# ZxUartAdapter.net
KiCad netlist of a schematic drawn in EAGLE
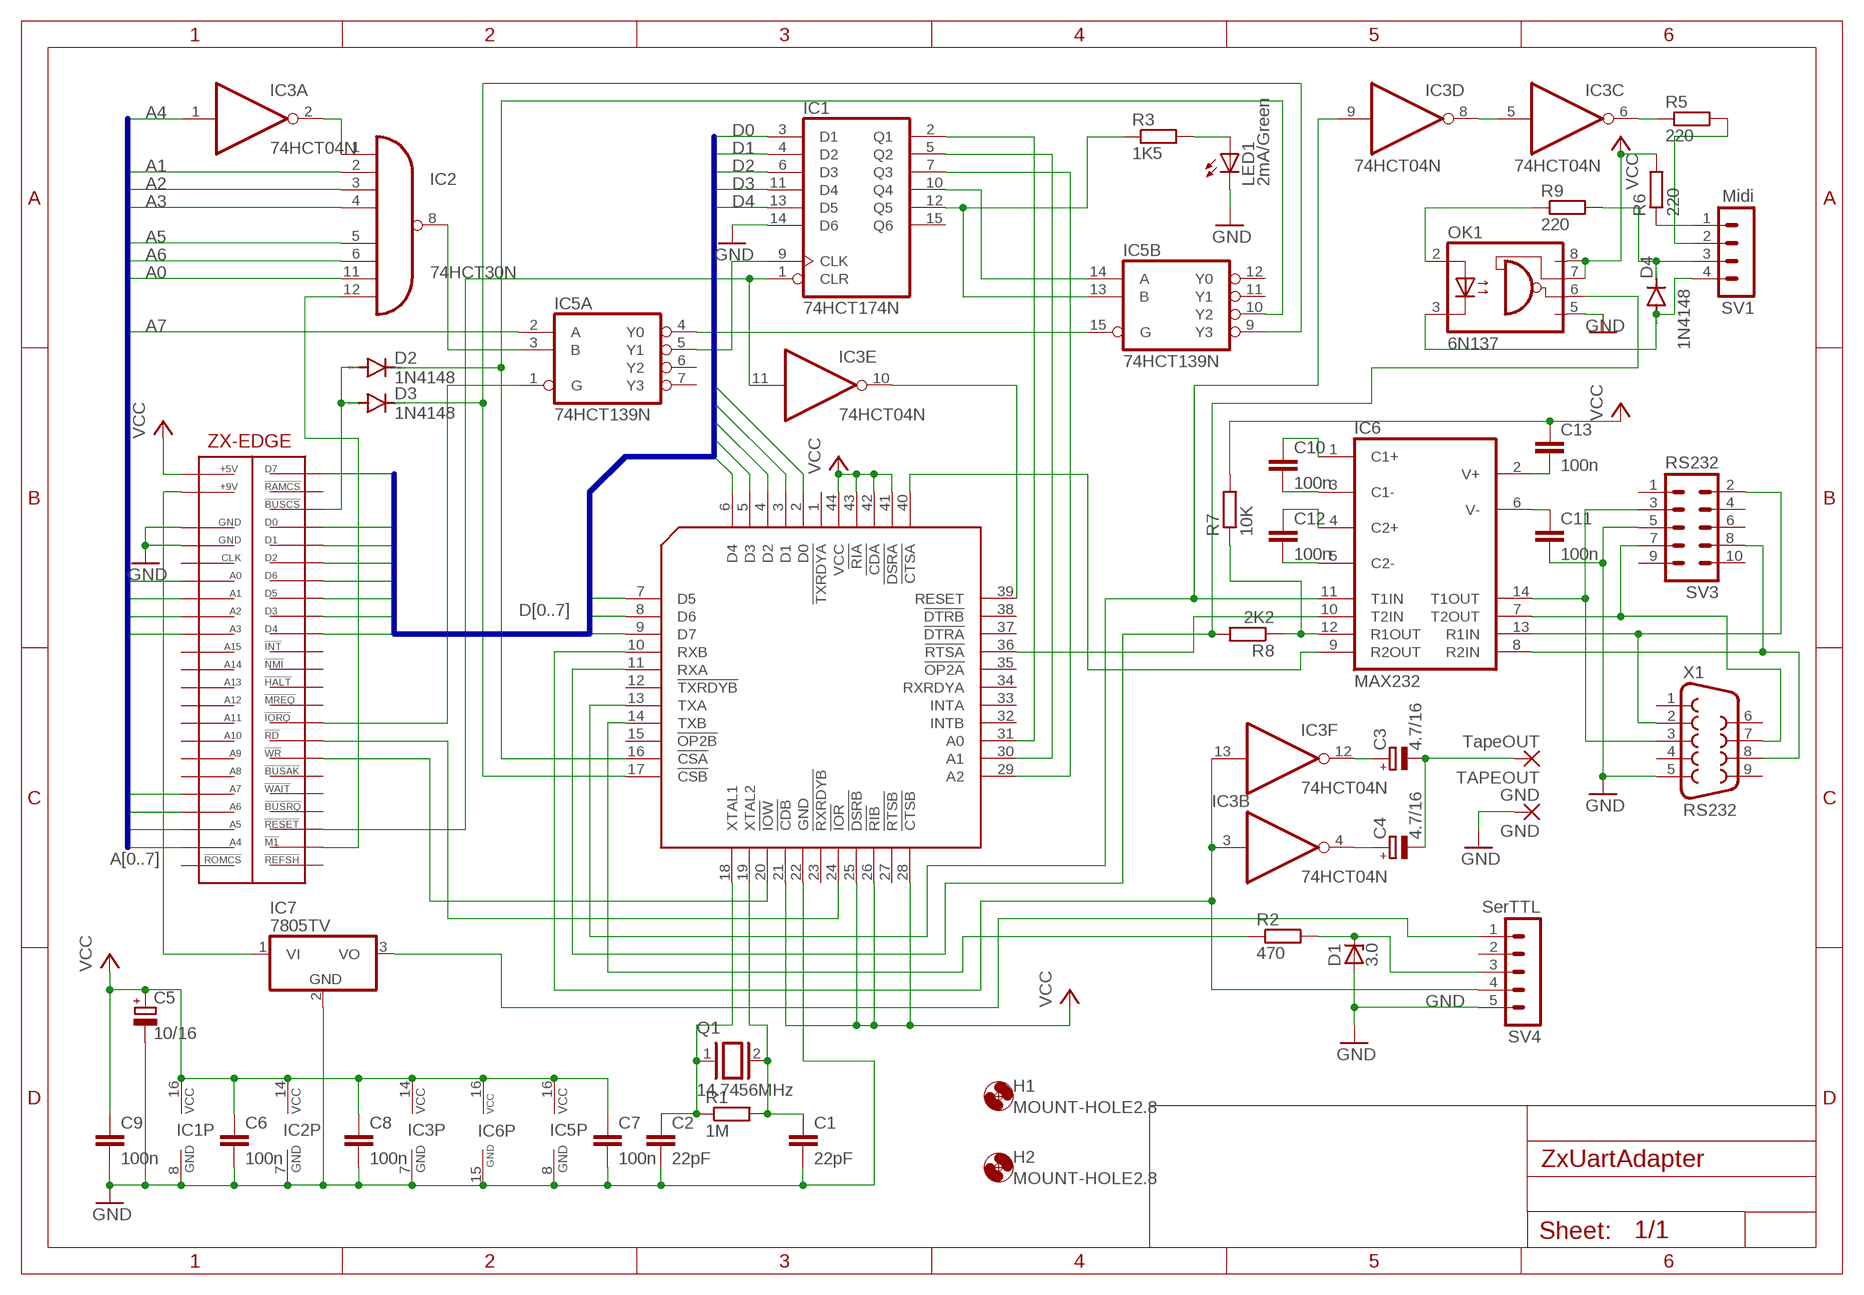
[diagram p0: schematic, sheet 1]

(export (version "E")
  (design (tool "Eeschema 10.0.6"))
  (components
    (comp (ref "C1")
      (value "22pF")
      (footprint "eagle-import:C025-025X050")
      (libsource (lib "eagle-import") (part "C-EU025-025X050"))
    )
    (comp (ref "C2")
      (value "22pF")
      (footprint "eagle-import:C025-025X050")
      (libsource (lib "eagle-import") (part "C-EU025-025X050"))
    )
    (comp (ref "C3")
      (value "4.7/16")
      (footprint "eagle-import:E5-5")
      (libsource (lib "eagle-import") (part "CPOL-EUE5-5"))
    )
    (comp (ref "C4")
      (value "4.7/16")
      (footprint "eagle-import:E5-5")
      (libsource (lib "eagle-import") (part "CPOL-EUE5-5"))
    )
    (comp (ref "C5")
      (value "10/16")
      (footprint "eagle-import:E5-6")
      (libsource (lib "eagle-import") (part "CPOL-EUE5-6"))
    )
    (comp (ref "C6")
      (value "100n")
      (footprint "eagle-import:C050-024X044")
      (libsource (lib "eagle-import") (part "C-EU050-024X044"))
    )
    (comp (ref "C7")
      (value "100n")
      (footprint "eagle-import:C050-024X044")
      (libsource (lib "eagle-import") (part "C-EU050-024X044"))
    )
    (comp (ref "C8")
      (value "100n")
      (footprint "eagle-import:C050-024X044")
      (libsource (lib "eagle-import") (part "C-EU050-024X044"))
    )
    (comp (ref "C9")
      (value "100n")
      (footprint "eagle-import:C050-024X044")
      (libsource (lib "eagle-import") (part "C-EU050-024X044"))
    )
    (comp (ref "C10")
      (value "100n")
      (footprint "eagle-import:C050-024X044")
      (libsource (lib "eagle-import") (part "C-EU050-024X044"))
    )
    (comp (ref "C11")
      (value "100n")
      (footprint "eagle-import:C050-024X044")
      (libsource (lib "eagle-import") (part "C-EU050-024X044"))
    )
    (comp (ref "C12")
      (value "100n")
      (footprint "eagle-import:C050-024X044")
      (libsource (lib "eagle-import") (part "C-EU050-024X044"))
    )
    (comp (ref "C13")
      (value "100n")
      (footprint "eagle-import:C050-024X044")
      (libsource (lib "eagle-import") (part "C-EU050-024X044"))
    )
    (comp (ref "D1")
      (value "3.0")
      (footprint "eagle-import:ZDIO-7.5")
      (libsource (lib "eagle-import") (part "ZENER-DIODEZD-7.5"))
    )
    (comp (ref "D2")
      (value "1N4148")
      (footprint "eagle-import:DO35-7")
      (libsource (lib "eagle-import") (part "1N4148DO35-7"))
    )
    (comp (ref "D3")
      (value "1N4148")
      (footprint "eagle-import:DO35-7")
      (libsource (lib "eagle-import") (part "1N4148DO35-7"))
    )
    (comp (ref "D4")
      (value "1N4148")
      (footprint "eagle-import:DO35-7")
      (libsource (lib "eagle-import") (part "1N4148DO35-7"))
    )
    (comp (ref "GND")
      (value "GND")
      (footprint "eagle-import:2,15_1,0")
      (libsource (lib "eagle-import") (part "2,15/1,0"))
    )
    (comp (ref "H1")
      (value "MOUNT-HOLE2.8")
      (footprint "eagle-import:2,8")
      (libsource (lib "eagle-import") (part "MOUNT-HOLE2.8"))
    )
    (comp (ref "H2")
      (value "MOUNT-HOLE2.8")
      (footprint "eagle-import:2,8")
      (libsource (lib "eagle-import") (part "MOUNT-HOLE2.8"))
    )
    (comp (ref "IC1")
      (value "74HCT174N")
      (footprint "eagle-import:DIL16")
      (libsource (lib "eagle-import") (part "74174NHCT"))
    )
    (comp (ref "IC2")
      (value "74HCT30N")
      (footprint "eagle-import:DIL14")
      (libsource (lib "eagle-import") (part "7430NHCT"))
    )
    (comp (ref "IC3")
      (value "74HCT04N")
      (footprint "eagle-import:DIL14")
      (libsource (lib "eagle-import") (part "7404NHCT"))
    )
    (comp (ref "IC4")
      (value "XR16C2850")
      (footprint "eagle-import:S44")
      (libsource (lib "eagle-import") (part "XR16C2850PLCC44S"))
    )
    (comp (ref "IC5")
      (value "74HCT139N")
      (footprint "eagle-import:DIL16")
      (libsource (lib "eagle-import") (part "74139NHCT"))
    )
    (comp (ref "IC6")
      (value "MAX232")
      (footprint "eagle-import:DIL16")
      (fields (field (name "MF") "MAXIM") (field (name "MPN") "MAX232ACPE+"))
      (libsource (lib "eagle-import") (part "MAX232"))
    )
    (comp (ref "IC7")
      (value "7805TV")
      (footprint "eagle-import:TO220V")
      (libsource (lib "eagle-import") (part "78TV05"))
    )
    (comp (ref "LED1")
      (value "2mA/Green")
      (footprint "eagle-import:LED3MM")
      (libsource (lib "eagle-import") (part "LED3MM"))
    )
    (comp (ref "OK1")
      (value "6N137")
      (footprint "eagle-import:DIL08")
      (libsource (lib "eagle-import") (part "6N137"))
    )
    (comp (ref "Q1")
      (value "14.7456MHz")
      (footprint "eagle-import:QS")
      (libsource (lib "eagle-import") (part "XTAL/S"))
    )
    (comp (ref "R1")
      (value "1M")
      (footprint "eagle-import:0207_12")
      (libsource (lib "eagle-import") (part "R-EU_0207/12"))
    )
    (comp (ref "R2")
      (value "470")
      (footprint "eagle-import:0207_12")
      (libsource (lib "eagle-import") (part "R-EU_0207/12"))
    )
    (comp (ref "R3")
      (value "1K5")
      (footprint "eagle-import:0207_12")
      (libsource (lib "eagle-import") (part "R-EU_0207/12"))
    )
    (comp (ref "R5")
      (value "220")
      (footprint "eagle-import:0207_12")
      (libsource (lib "eagle-import") (part "R-EU_0207/12"))
    )
    (comp (ref "R6")
      (value "220")
      (footprint "eagle-import:0207_12")
      (libsource (lib "eagle-import") (part "R-EU_0207/12"))
    )
    (comp (ref "R7")
      (value "10K")
      (footprint "eagle-import:0207_12")
      (libsource (lib "eagle-import") (part "R-EU_0207/12"))
    )
    (comp (ref "R8")
      (value "2K2")
      (footprint "eagle-import:0207_12")
      (libsource (lib "eagle-import") (part "R-EU_0207/12"))
    )
    (comp (ref "R9")
      (value "220")
      (footprint "eagle-import:0207_12")
      (libsource (lib "eagle-import") (part "R-EU_0207/12"))
    )
    (comp (ref "SV1")
      (value "Midi")
      (footprint "eagle-import:MA04-1")
      (libsource (lib "eagle-import") (part "MA04-1"))
    )
    (comp (ref "SV3")
      (value "RS232")
      (footprint "eagle-import:MA05-2")
      (libsource (lib "eagle-import") (part "MA05-2"))
    )
    (comp (ref "SV4")
      (value "SerTTL")
      (footprint "eagle-import:MA05-1")
      (libsource (lib "eagle-import") (part "MA05-1"))
    )
    (comp (ref "TAPEOUT")
      (value "TapeOUT")
      (footprint "eagle-import:2,15_1,0")
      (libsource (lib "eagle-import") (part "2,15/1,0"))
    )
    (comp (ref "U$1")
      (value "ZX-EDGEZX96")
      (footprint "eagle-import:ZX-EDGE64")
      (libsource (lib "eagle-import") (part "ZX-EDGEZX96"))
    )
    (comp (ref "X1")
      (value "RS232")
      (footprint "eagle-import:F09HP")
      (libsource (lib "eagle-import") (part "F09HP"))
    )
  )
  (nets
    (net (code "1") (name "/A0") (class "Default")
      (node (ref "IC2") (pin "11") (pinfunction "I6_11") (pintype "input"))
      (node (ref "U$1") (pin "A21") (pinfunction "A0_A21") (pintype "bidirectional"))
    )
    (net (code "2") (name "/A1") (class "Default")
      (node (ref "IC2") (pin "2") (pinfunction "I1_2") (pintype "input"))
      (node (ref "U$1") (pin "A20") (pinfunction "A1_A20") (pintype "bidirectional"))
    )
    (net (code "3") (name "/A2") (class "Default")
      (node (ref "IC2") (pin "3") (pinfunction "I2_3") (pintype "input"))
      (node (ref "U$1") (pin "A19") (pinfunction "A2_A19") (pintype "bidirectional"))
    )
    (net (code "4") (name "/A3") (class "Default")
      (node (ref "IC2") (pin "4") (pinfunction "I3_4") (pintype "input"))
      (node (ref "U$1") (pin "A18") (pinfunction "A3_A18") (pintype "bidirectional"))
    )
    (net (code "5") (name "/A4") (class "Default")
      (node (ref "IC3") (pin "1") (pinfunction "I_1") (pintype "input"))
      (node (ref "U$1") (pin "A6") (pinfunction "A4_A6") (pintype "bidirectional"))
    )
    (net (code "6") (name "/A5") (class "Default")
      (node (ref "IC2") (pin "5") (pinfunction "I4_5") (pintype "input"))
      (node (ref "U$1") (pin "A7") (pinfunction "A5_A7") (pintype "bidirectional"))
    )
    (net (code "7") (name "/A6") (class "Default")
      (node (ref "IC2") (pin "6") (pinfunction "I5_6") (pintype "input"))
      (node (ref "U$1") (pin "A8") (pinfunction "A6_A8") (pintype "bidirectional"))
    )
    (net (code "8") (name "/A7") (class "Default")
      (node (ref "IC5") (pin "2") (pinfunction "A_2") (pintype "input"))
      (node (ref "U$1") (pin "A9") (pinfunction "A7_A9") (pintype "bidirectional"))
    )
    (net (code "10") (name "/D0") (class "Default")
      (node (ref "IC1") (pin "3") (pinfunction "D1_3") (pintype "input"))
      (node (ref "IC4") (pin "2") (pinfunction "D0_2") (pintype "bidirectional"))
      (node (ref "U$1") (pin "C24") (pinfunction "D0_C24") (pintype "bidirectional"))
    )
    (net (code "11") (name "/D1") (class "Default")
      (node (ref "IC1") (pin "4") (pinfunction "D2_4") (pintype "input"))
      (node (ref "IC4") (pin "3") (pinfunction "D1_3") (pintype "bidirectional"))
      (node (ref "U$1") (pin "C23") (pinfunction "D1_C23") (pintype "bidirectional"))
    )
    (net (code "12") (name "/D2") (class "Default")
      (node (ref "IC1") (pin "6") (pinfunction "D3_6") (pintype "input"))
      (node (ref "IC4") (pin "4") (pinfunction "D2_4") (pintype "bidirectional"))
      (node (ref "U$1") (pin "C22") (pinfunction "D2_C22") (pintype "bidirectional"))
    )
    (net (code "13") (name "/D3") (class "Default")
      (node (ref "IC1") (pin "11") (pinfunction "D4_11") (pintype "input"))
      (node (ref "IC4") (pin "5") (pinfunction "D3_5") (pintype "bidirectional"))
      (node (ref "U$1") (pin "C19") (pinfunction "D3_C19") (pintype "bidirectional"))
    )
    (net (code "14") (name "/D4") (class "Default")
      (node (ref "IC1") (pin "13") (pinfunction "D5_13") (pintype "input"))
      (node (ref "IC4") (pin "6") (pinfunction "D4_6") (pintype "bidirectional"))
      (node (ref "U$1") (pin "C18") (pinfunction "D4_C18") (pintype "bidirectional"))
    )
    (net (code "15") (name "/D5") (class "Default")
      (node (ref "IC4") (pin "7") (pinfunction "D5_7") (pintype "bidirectional"))
      (node (ref "U$1") (pin "C20") (pinfunction "D5_C20") (pintype "bidirectional"))
    )
    (net (code "16") (name "/D6") (class "Default")
      (node (ref "IC4") (pin "8") (pinfunction "D6_8") (pintype "bidirectional"))
      (node (ref "U$1") (pin "C21") (pinfunction "D6_C21") (pintype "bidirectional"))
    )
    (net (code "17") (name "/D7") (class "Default")
      (node (ref "IC4") (pin "9") (pinfunction "D7_9") (pintype "bidirectional"))
      (node (ref "U$1") (pin "C27") (pinfunction "D7_C27") (pintype "bidirectional"))
    )
    (net (code "19") (name "GND") (class "Default")
      (node (ref "C1") (pin "2") (pinfunction "2_2") (pintype "passive"))
      (node (ref "C11") (pin "2") (pinfunction "2_2") (pintype "passive"))
      (node (ref "C2") (pin "2") (pinfunction "2_2") (pintype "passive"))
      (node (ref "C5") (pin "-") (pinfunction "-_-") (pintype "passive"))
      (node (ref "C6") (pin "2") (pinfunction "2_2") (pintype "passive"))
      (node (ref "C7") (pin "2") (pinfunction "2_2") (pintype "passive"))
      (node (ref "C8") (pin "2") (pinfunction "2_2") (pintype "passive"))
      (node (ref "C9") (pin "2") (pinfunction "2_2") (pintype "passive"))
      (node (ref "D1") (pin "A") (pinfunction "A_A") (pintype "passive"))
      (node (ref "GND") (pin "1") (pinfunction "P_1") (pintype "passive"))
      (node (ref "IC1") (pin "14") (pinfunction "D6_14") (pintype "input"))
      (node (ref "IC1") (pin "8") (pinfunction "GND_8") (pintype "power_in"))
      (node (ref "IC2") (pin "7") (pinfunction "GND_7") (pintype "power_in"))
      (node (ref "IC3") (pin "7") (pinfunction "GND_7") (pintype "power_in"))
      (node (ref "IC4") (pin "22") (pinfunction "GND_22") (pintype "power_in"))
      (node (ref "IC5") (pin "8") (pinfunction "GND_8") (pintype "power_in"))
      (node (ref "IC6") (pin "15") (pinfunction "GND_15") (pintype "power_in"))
      (node (ref "IC7") (pin "2") (pinfunction "GND_2") (pintype "passive"))
      (node (ref "LED1") (pin "K") (pinfunction "C_K") (pintype "passive"))
      (node (ref "OK1") (pin "5") (pinfunction "GND_5") (pintype "passive"))
      (node (ref "SV3") (pin "5") (pinfunction "5_5") (pintype "passive"))
      (node (ref "SV4") (pin "5") (pinfunction "5_5") (pintype "passive"))
      (node (ref "U$1") (pin "A23") (pinfunction "GND2_A23") (pintype "bidirectional"))
      (node (ref "U$1") (pin "A24") (pinfunction "GND1_A24") (pintype "bidirectional"))
      (node (ref "X1") (pin "5") (pinfunction "5_5") (pintype "passive"))
    )
    (net (code "20") (name "Net-(D1-PadC)") (class "Default")
      (node (ref "D1") (pin "C") (pinfunction "C_C") (pintype "passive"))
      (node (ref "R2") (pin "2") (pinfunction "2_2") (pintype "passive"))
      (node (ref "SV4") (pin "3") (pinfunction "3_3") (pintype "passive"))
    )
    (net (code "21") (name "Net-(D4-PadC)") (class "Default")
      (node (ref "D4") (pin "C") (pinfunction "C_C") (pintype "passive"))
      (node (ref "R9") (pin "2") (pinfunction "2_2") (pintype "passive"))
      (node (ref "SV1") (pin "3") (pinfunction "3_3") (pintype "passive"))
    )
    (net (code "22") (name "Net-(IC1A-CLK)") (class "Default")
      (node (ref "IC1") (pin "9") (pinfunction "CLK_9") (pintype "input"))
      (node (ref "IC5") (pin "5") (pinfunction "Y1_5") (pintype "output"))
    )
    (net (code "23") (name "Net-(IC1A-CLR)") (class "Default")
      (node (ref "IC1") (pin "1") (pinfunction "CLR_1") (pintype "input"))
      (node (ref "IC3") (pin "11") (pinfunction "I_11") (pintype "input"))
      (node (ref "U$1") (pin "C7") (pinfunction "~{RESET}_C7") (pintype "bidirectional"))
    )
    (net (code "24") (name "Net-(IC1A-Q1)") (class "Default")
      (node (ref "IC1") (pin "2") (pinfunction "Q1_2") (pintype "output"))
      (node (ref "IC4") (pin "31") (pinfunction "A0_31") (pintype "input"))
    )
    (net (code "25") (name "Net-(IC1A-Q2)") (class "Default")
      (node (ref "IC1") (pin "5") (pinfunction "Q2_5") (pintype "output"))
      (node (ref "IC4") (pin "30") (pinfunction "A1_30") (pintype "input"))
    )
    (net (code "26") (name "Net-(IC1A-Q3)") (class "Default")
      (node (ref "IC1") (pin "7") (pinfunction "Q3_7") (pintype "output"))
      (node (ref "IC4") (pin "29") (pinfunction "A2_29") (pintype "input"))
    )
    (net (code "27") (name "Net-(IC1A-Q4)") (class "Default")
      (node (ref "IC1") (pin "10") (pinfunction "Q4_10") (pintype "output"))
      (node (ref "IC5") (pin "14") (pinfunction "A_14") (pintype "input"))
    )
    (net (code "28") (name "Net-(IC1A-Q5)") (class "Default")
      (node (ref "IC1") (pin "12") (pinfunction "Q5_12") (pintype "output"))
      (node (ref "IC5") (pin "13") (pinfunction "B_13") (pintype "input"))
      (node (ref "R3") (pin "1") (pinfunction "1_1") (pintype "passive"))
    )
    (net (code "29") (name "Net-(IC2A-I0)") (class "Default")
      (node (ref "IC2") (pin "1") (pinfunction "I0_1") (pintype "input"))
      (node (ref "IC3") (pin "2") (pinfunction "O_2") (pintype "output"))
    )
    (net (code "30") (name "Net-(IC2A-I7)") (class "Default")
      (node (ref "IC2") (pin "12") (pinfunction "I7_12") (pintype "input"))
      (node (ref "U$1") (pin "C6") (pinfunction "~{M1}_C6") (pintype "bidirectional"))
    )
    (net (code "31") (name "Net-(IC2A-O)") (class "Default")
      (node (ref "IC2") (pin "8") (pinfunction "O_8") (pintype "output"))
      (node (ref "IC5") (pin "3") (pinfunction "B_3") (pintype "input"))
    )
    (net (code "32") (name "Net-(IC3B-I)") (class "Default")
      (node (ref "IC3") (pin "13") (pinfunction "I_13") (pintype "input"))
      (node (ref "IC3") (pin "3") (pinfunction "I_3") (pintype "input"))
      (node (ref "IC4") (pin "10") (pinfunction "RXB_10") (pintype "input"))
      (node (ref "SV4") (pin "4") (pinfunction "4_4") (pintype "passive"))
    )
    (net (code "33") (name "Net-(IC3B-O)") (class "Default")
      (node (ref "C4") (pin "+") (pinfunction "+_+") (pintype "passive"))
      (node (ref "IC3") (pin "4") (pinfunction "O_4") (pintype "output"))
    )
    (net (code "34") (name "Net-(IC3C-I)") (class "Default")
      (node (ref "IC3") (pin "5") (pinfunction "I_5") (pintype "input"))
      (node (ref "IC3") (pin "8") (pinfunction "O_8") (pintype "output"))
    )
    (net (code "35") (name "Net-(IC3C-O)") (class "Default")
      (node (ref "IC3") (pin "6") (pinfunction "O_6") (pintype "output"))
      (node (ref "R5") (pin "1") (pinfunction "1_1") (pintype "passive"))
    )
    (net (code "36") (name "Net-(IC3D-I)") (class "Default")
      (node (ref "IC3") (pin "9") (pinfunction "I_9") (pintype "input"))
      (node (ref "IC4") (pin "13") (pinfunction "TXA_13") (pintype "output"))
      (node (ref "IC6") (pin "11") (pinfunction "T1IN_11") (pintype "input"))
    )
    (net (code "37") (name "Net-(IC3E-O)") (class "Default")
      (node (ref "IC3") (pin "10") (pinfunction "O_10") (pintype "output"))
      (node (ref "IC4") (pin "39") (pinfunction "RESET_39") (pintype "input"))
    )
    (net (code "38") (name "Net-(IC3F-O)") (class "Default")
      (node (ref "C3") (pin "+") (pinfunction "+_+") (pintype "passive"))
      (node (ref "IC3") (pin "12") (pinfunction "O_12") (pintype "output"))
    )
    (net (code "39") (name "Net-(IC4-RXA)") (class "Default")
      (node (ref "IC4") (pin "11") (pinfunction "RXA_11") (pintype "input"))
      (node (ref "OK1") (pin "6") (pinfunction "VO_6") (pintype "passive"))
      (node (ref "R8") (pin "2") (pinfunction "2_2") (pintype "passive"))
    )
    (net (code "40") (name "Net-(IC4-TXB)") (class "Default")
      (node (ref "IC4") (pin "14") (pinfunction "TXB_14") (pintype "input"))
      (node (ref "R2") (pin "1") (pinfunction "1_1") (pintype "passive"))
    )
    (net (code "41") (name "Net-(IC4-XTAL1)") (class "Default")
      (node (ref "C2") (pin "1") (pinfunction "1_1") (pintype "passive"))
      (node (ref "IC4") (pin "18") (pinfunction "XTAL1_18") (pintype "input"))
      (node (ref "Q1") (pin "1") (pinfunction "1_1") (pintype "passive"))
      (node (ref "R1") (pin "1") (pinfunction "1_1") (pintype "passive"))
    )
    (net (code "42") (name "Net-(IC4-XTAL2)") (class "Default")
      (node (ref "C1") (pin "1") (pinfunction "1_1") (pintype "passive"))
      (node (ref "IC4") (pin "19") (pinfunction "XTAL2_19") (pintype "output"))
      (node (ref "Q1") (pin "2") (pinfunction "2_2") (pintype "passive"))
      (node (ref "R1") (pin "2") (pinfunction "2_2") (pintype "passive"))
    )
    (net (code "43") (name "Net-(IC4-~{CSA})") (class "Default")
      (node (ref "D2") (pin "C") (pinfunction "C_C") (pintype "passive"))
      (node (ref "IC4") (pin "16") (pinfunction "~{CSA}_16") (pintype "input"))
      (node (ref "IC5") (pin "10") (pinfunction "Y2_10") (pintype "output"))
    )
    (net (code "44") (name "Net-(IC4-~{CSB})") (class "Default")
      (node (ref "D3") (pin "C") (pinfunction "C_C") (pintype "passive"))
      (node (ref "IC4") (pin "17") (pinfunction "~{CSB}_17") (pintype "input"))
      (node (ref "IC5") (pin "9") (pinfunction "Y3_9") (pintype "output"))
    )
    (net (code "45") (name "Net-(IC4-~{CTSA})") (class "Default")
      (node (ref "IC4") (pin "40") (pinfunction "~{CTSA}_40") (pintype "input"))
      (node (ref "IC6") (pin "9") (pinfunction "R2OUT_9") (pintype "output"))
    )
    (net (code "46") (name "Net-(IC4-~{IOR})") (class "Default")
      (node (ref "IC4") (pin "24") (pinfunction "~{IOR}_24") (pintype "input"))
      (node (ref "U$1") (pin "C12") (pinfunction "~{RD}_C12") (pintype "bidirectional"))
    )
    (net (code "47") (name "Net-(IC4-~{IOW})") (class "Default")
      (node (ref "IC4") (pin "20") (pinfunction "~{IOW}_20") (pintype "input"))
      (node (ref "U$1") (pin "C11") (pinfunction "~{WR}_C11") (pintype "bidirectional"))
    )
    (net (code "48") (name "Net-(IC4-~{RTSA})") (class "Default")
      (node (ref "IC4") (pin "36") (pinfunction "~{RTSA}_36") (pintype "output"))
      (node (ref "IC6") (pin "10") (pinfunction "T2IN_10") (pintype "input"))
    )
    (net (code "49") (name "Net-(IC5A-G)") (class "Default")
      (node (ref "IC5") (pin "1") (pinfunction "G_1") (pintype "input"))
      (node (ref "U$1") (pin "C13") (pinfunction "~{IORQ}_C13") (pintype "bidirectional"))
    )
    (net (code "50") (name "Net-(IC5A-Y0)") (class "Default")
      (node (ref "IC5") (pin "15") (pinfunction "G_15") (pintype "input"))
      (node (ref "IC5") (pin "4") (pinfunction "Y0_4") (pintype "output"))
    )
    (net (code "51") (name "Net-(IC6A-C1+)") (class "Default")
      (node (ref "C10") (pin "1") (pinfunction "1_1") (pintype "passive"))
      (node (ref "IC6") (pin "1") (pinfunction "C1+_1") (pintype "bidirectional"))
    )
    (net (code "52") (name "Net-(IC6A-C1-)") (class "Default")
      (node (ref "C10") (pin "2") (pinfunction "2_2") (pintype "passive"))
      (node (ref "IC6") (pin "3") (pinfunction "C1-_3") (pintype "bidirectional"))
    )
    (net (code "53") (name "Net-(IC6A-C2+)") (class "Default")
      (node (ref "C12") (pin "1") (pinfunction "1_1") (pintype "passive"))
      (node (ref "IC6") (pin "4") (pinfunction "C2+_4") (pintype "bidirectional"))
    )
    (net (code "54") (name "Net-(IC6A-C2-)") (class "Default")
      (node (ref "C12") (pin "2") (pinfunction "2_2") (pintype "passive"))
      (node (ref "IC6") (pin "5") (pinfunction "C2-_5") (pintype "bidirectional"))
    )
    (net (code "55") (name "Net-(IC6A-R1IN)") (class "Default")
      (node (ref "IC6") (pin "13") (pinfunction "R1IN_13") (pintype "input"))
      (node (ref "SV3") (pin "2") (pinfunction "2_2") (pintype "passive"))
      (node (ref "X1") (pin "2") (pinfunction "2_2") (pintype "passive"))
    )
    (net (code "56") (name "Net-(IC6A-R1OUT)") (class "Default")
      (node (ref "IC6") (pin "12") (pinfunction "R1OUT_12") (pintype "output"))
      (node (ref "R7") (pin "1") (pinfunction "1_1") (pintype "passive"))
      (node (ref "R8") (pin "1") (pinfunction "1_1") (pintype "passive"))
    )
    (net (code "57") (name "Net-(IC6A-R2IN)") (class "Default")
      (node (ref "IC6") (pin "8") (pinfunction "R2IN_8") (pintype "input"))
      (node (ref "SV3") (pin "8") (pinfunction "8_8") (pintype "passive"))
      (node (ref "X1") (pin "8") (pinfunction "8_8") (pintype "passive"))
    )
    (net (code "58") (name "Net-(IC6A-T1OUT)") (class "Default")
      (node (ref "IC6") (pin "14") (pinfunction "T1OUT_14") (pintype "output"))
      (node (ref "SV3") (pin "3") (pinfunction "3_3") (pintype "passive"))
      (node (ref "X1") (pin "3") (pinfunction "3_3") (pintype "passive"))
    )
    (net (code "59") (name "Net-(IC6A-T2OUT)") (class "Default")
      (node (ref "IC6") (pin "7") (pinfunction "T2OUT_7") (pintype "output"))
      (node (ref "SV3") (pin "7") (pinfunction "7_7") (pintype "passive"))
      (node (ref "X1") (pin "7") (pinfunction "7_7") (pintype "passive"))
    )
    (net (code "60") (name "Net-(IC6A-V+)") (class "Default")
      (node (ref "C13") (pin "2") (pinfunction "2_2") (pintype "passive"))
      (node (ref "IC6") (pin "2") (pinfunction "V+_2") (pintype "bidirectional"))
    )
    (net (code "61") (name "Net-(IC6A-V-)") (class "Default")
      (node (ref "C11") (pin "1") (pinfunction "1_1") (pintype "passive"))
      (node (ref "IC6") (pin "6") (pinfunction "V-_6") (pintype "bidirectional"))
    )
    (net (code "62") (name "Net-(IC7-VI)") (class "Default")
      (node (ref "IC7") (pin "1") (pinfunction "VI_1") (pintype "input"))
      (node (ref "U$1") (pin "A26") (pinfunction "+9_A26") (pintype "bidirectional"))
    )
    (net (code "63") (name "Net-(IC7-VO)") (class "Default")
      (node (ref "IC7") (pin "3") (pinfunction "VO_3") (pintype "passive"))
      (node (ref "SV4") (pin "1") (pinfunction "1_1") (pintype "passive"))
    )
    (net (code "64") (name "Net-(LED1-PadA)") (class "Default")
      (node (ref "LED1") (pin "A") (pinfunction "A_A") (pintype "passive"))
      (node (ref "R3") (pin "2") (pinfunction "2_2") (pintype "passive"))
    )
    (net (code "65") (name "Net-(OK1-A)") (class "Default")
      (node (ref "OK1") (pin "2") (pinfunction "A_2") (pintype "passive"))
      (node (ref "R9") (pin "1") (pinfunction "1_1") (pintype "passive"))
    )
    (net (code "66") (name "Net-(OK1-C)") (class "Default")
      (node (ref "D4") (pin "A") (pinfunction "A_A") (pintype "passive"))
      (node (ref "OK1") (pin "3") (pinfunction "C_3") (pintype "passive"))
      (node (ref "SV1") (pin "4") (pinfunction "4_4") (pintype "passive"))
    )
    (net (code "67") (name "Net-(R5-Pad2)") (class "Default")
      (node (ref "R5") (pin "2") (pinfunction "2_2") (pintype "passive"))
      (node (ref "SV1") (pin "2") (pinfunction "2_2") (pintype "passive"))
    )
    (net (code "68") (name "Net-(R6-Pad1)") (class "Default")
      (node (ref "R6") (pin "1") (pinfunction "1_1") (pintype "passive"))
      (node (ref "SV1") (pin "1") (pinfunction "1_1") (pintype "passive"))
    )
    (net (code "69") (name "Net-(TAPEOUT-P)") (class "Default")
      (node (ref "C3") (pin "-") (pinfunction "-_-") (pintype "passive"))
      (node (ref "C4") (pin "-") (pinfunction "-_-") (pintype "passive"))
      (node (ref "TAPEOUT") (pin "1") (pinfunction "P_1") (pintype "passive"))
    )
    (net (code "70") (name "Net-(U$1-~{BUSCS})") (class "Default")
      (node (ref "D2") (pin "A") (pinfunction "A_A") (pintype "passive"))
      (node (ref "D3") (pin "A") (pinfunction "A_A") (pintype "passive"))
      (node (ref "U$1") (pin "C25") (pinfunction "~{BUSCS}_C25") (pintype "bidirectional"))
    )
    (net (code "71") (name "VCC") (class "Default")
      (node (ref "C13") (pin "1") (pinfunction "1_1") (pintype "passive"))
      (node (ref "C5") (pin "+") (pinfunction "+_+") (pintype "passive"))
      (node (ref "C6") (pin "1") (pinfunction "1_1") (pintype "passive"))
      (node (ref "C7") (pin "1") (pinfunction "1_1") (pintype "passive"))
      (node (ref "C8") (pin "1") (pinfunction "1_1") (pintype "passive"))
      (node (ref "C9") (pin "1") (pinfunction "1_1") (pintype "passive"))
      (node (ref "IC1") (pin "16") (pinfunction "VCC_16") (pintype "power_in"))
      (node (ref "IC2") (pin "14") (pinfunction "VCC_14") (pintype "power_in"))
      (node (ref "IC3") (pin "14") (pinfunction "VCC_14") (pintype "power_in"))
      (node (ref "IC4") (pin "21") (pinfunction "~{CDB}_21") (pintype "input"))
      (node (ref "IC4") (pin "25") (pinfunction "~{DSRB}_25") (pintype "input"))
      (node (ref "IC4") (pin "26") (pinfunction "~{RIB}_26") (pintype "input"))
      (node (ref "IC4") (pin "28") (pinfunction "~{CTSB}_28") (pintype "input"))
      (node (ref "IC4") (pin "41") (pinfunction "~{DSRA}_41") (pintype "input"))
      (node (ref "IC4") (pin "42") (pinfunction "~{CDA}_42") (pintype "input"))
      (node (ref "IC4") (pin "43") (pinfunction "~{RIA}_43") (pintype "input"))
      (node (ref "IC4") (pin "44") (pinfunction "VCC_44") (pintype "power_in"))
      (node (ref "IC5") (pin "16") (pinfunction "VCC_16") (pintype "power_in"))
      (node (ref "IC6") (pin "16") (pinfunction "VCC_16") (pintype "power_in"))
      (node (ref "OK1") (pin "7") (pinfunction "VE_7") (pintype "passive"))
      (node (ref "OK1") (pin "8") (pinfunction "VCC_8") (pintype "passive"))
      (node (ref "R6") (pin "2") (pinfunction "2_2") (pintype "passive"))
      (node (ref "R7") (pin "2") (pinfunction "2_2") (pintype "passive"))
      (node (ref "U$1") (pin "A27") (pinfunction "+5_A27") (pintype "bidirectional"))
    )
    (net (code "72") (name "unconnected-(IC1A-Q6-Pad15)") (class "Default")
      (node (ref "IC1") (pin "15") (pinfunction "Q6_15") (pintype "output"))
    )
    (net (code "73") (name "unconnected-(IC4-INTA-Pad33)") (class "Default")
      (node (ref "IC4") (pin "33") (pinfunction "INTA_33") (pintype "output"))
    )
    (net (code "74") (name "unconnected-(IC4-INTB-Pad32)") (class "Default")
      (node (ref "IC4") (pin "32") (pinfunction "INTB_32") (pintype "output"))
    )
    (net (code "75") (name "unconnected-(IC4-RXRDYA-Pad34)") (class "Default")
      (node (ref "IC4") (pin "34") (pinfunction "RXRDYA_34") (pintype "output"))
    )
    (net (code "76") (name "unconnected-(IC4-~{DTRA}-Pad37)") (class "Default")
      (node (ref "IC4") (pin "37") (pinfunction "~{DTRA}_37") (pintype "output"))
    )
    (net (code "77") (name "unconnected-(IC4-~{DTRB}-Pad38)") (class "Default")
      (node (ref "IC4") (pin "38") (pinfunction "~{DTRB}_38") (pintype "output"))
    )
    (net (code "78") (name "unconnected-(IC4-~{OP2A}-Pad35)") (class "Default")
      (node (ref "IC4") (pin "35") (pinfunction "~{OP2A}_35") (pintype "output"))
    )
    (net (code "79") (name "unconnected-(IC4-~{OP2B}-Pad15)") (class "Default")
      (node (ref "IC4") (pin "15") (pinfunction "~{OP2B}_15") (pintype "output"))
    )
    (net (code "80") (name "unconnected-(IC4-~{RTSB}-Pad27)") (class "Default")
      (node (ref "IC4") (pin "27") (pinfunction "~{RTSB}_27") (pintype "output"))
    )
    (net (code "81") (name "unconnected-(IC4-~{RXRDYB}-Pad23)") (class "Default")
      (node (ref "IC4") (pin "23") (pinfunction "~{RXRDYB}_23") (pintype "output"))
    )
    (net (code "82") (name "unconnected-(IC4-~{TXRDYA}-Pad1)") (class "Default")
      (node (ref "IC4") (pin "1") (pinfunction "~{TXRDYA}_1") (pintype "output"))
    )
    (net (code "83") (name "unconnected-(IC4-~{TXRDYB}-Pad12)") (class "Default")
      (node (ref "IC4") (pin "12") (pinfunction "~{TXRDYB}_12") (pintype "output"))
    )
    (net (code "84") (name "unconnected-(IC5A-Y2-Pad6)") (class "Default")
      (node (ref "IC5") (pin "6") (pinfunction "Y2_6") (pintype "output"))
    )
    (net (code "85") (name "unconnected-(IC5A-Y3-Pad7)") (class "Default")
      (node (ref "IC5") (pin "7") (pinfunction "Y3_7") (pintype "output"))
    )
    (net (code "86") (name "unconnected-(IC5B-Y0-Pad12)") (class "Default")
      (node (ref "IC5") (pin "12") (pinfunction "Y0_12") (pintype "output"))
    )
    (net (code "87") (name "unconnected-(IC5B-Y1-Pad11)") (class "Default")
      (node (ref "IC5") (pin "11") (pinfunction "Y1_11") (pintype "output"))
    )
    (net (code "88") (name "unconnected-(SV3-Pad1)") (class "Default")
      (node (ref "SV3") (pin "1") (pinfunction "1_1") (pintype "passive"))
    )
    (net (code "89") (name "unconnected-(SV3-Pad4)") (class "Default")
      (node (ref "SV3") (pin "4") (pinfunction "4_4") (pintype "passive"))
    )
    (net (code "90") (name "unconnected-(SV3-Pad6)") (class "Default")
      (node (ref "SV3") (pin "6") (pinfunction "6_6") (pintype "passive"))
    )
    (net (code "91") (name "unconnected-(SV3-Pad9)") (class "Default")
      (node (ref "SV3") (pin "9") (pinfunction "9_9") (pintype "passive"))
    )
    (net (code "92") (name "unconnected-(SV3-Pad10)") (class "Default")
      (node (ref "SV3") (pin "10") (pinfunction "10_10") (pintype "passive"))
    )
    (net (code "93") (name "unconnected-(SV4-Pad2)") (class "Default")
      (node (ref "SV4") (pin "2") (pinfunction "2_2") (pintype "passive"))
    )
    (net (code "94") (name "unconnected-(U$1-A8-PadA10)") (class "Default")
      (node (ref "U$1") (pin "A10") (pinfunction "A8_A10") (pintype "bidirectional"))
    )
    (net (code "95") (name "unconnected-(U$1-A9-PadA11)") (class "Default")
      (node (ref "U$1") (pin "A11") (pinfunction "A9_A11") (pintype "bidirectional"))
    )
    (net (code "96") (name "unconnected-(U$1-A10-PadA12)") (class "Default")
      (node (ref "U$1") (pin "A12") (pinfunction "A10_A12") (pintype "bidirectional"))
    )
    (net (code "97") (name "unconnected-(U$1-A11-PadA13)") (class "Default")
      (node (ref "U$1") (pin "A13") (pinfunction "A11_A13") (pintype "bidirectional"))
    )
    (net (code "98") (name "unconnected-(U$1-A12-PadA14)") (class "Default")
      (node (ref "U$1") (pin "A14") (pinfunction "A12_A14") (pintype "bidirectional"))
    )
    (net (code "99") (name "unconnected-(U$1-A13-PadA15)") (class "Default")
      (node (ref "U$1") (pin "A15") (pinfunction "A13_A15") (pintype "bidirectional"))
    )
    (net (code "100") (name "unconnected-(U$1-A14-PadA16)") (class "Default")
      (node (ref "U$1") (pin "A16") (pinfunction "A14_A16") (pintype "bidirectional"))
    )
    (net (code "101") (name "unconnected-(U$1-A15-PadA17)") (class "Default")
      (node (ref "U$1") (pin "A17") (pinfunction "A15_A17") (pintype "bidirectional"))
    )
    (net (code "102") (name "unconnected-(U$1-CLK-PadA22)") (class "Default")
      (node (ref "U$1") (pin "A22") (pinfunction "CLK_A22") (pintype "bidirectional"))
    )
    (net (code "103") (name "unconnected-(U$1-~{BUSAK}-PadC10)") (class "Default")
      (node (ref "U$1") (pin "C10") (pinfunction "~{BUSAK}_C10") (pintype "bidirectional"))
    )
    (net (code "104") (name "unconnected-(U$1-~{BUSRQ}-PadC8)") (class "Default")
      (node (ref "U$1") (pin "C8") (pinfunction "~{BUSRQ}_C8") (pintype "bidirectional"))
    )
    (net (code "105") (name "unconnected-(U$1-~{HALT}-PadC15)") (class "Default")
      (node (ref "U$1") (pin "C15") (pinfunction "~{HALT}_C15") (pintype "bidirectional"))
    )
    (net (code "106") (name "unconnected-(U$1-~{INT}-PadC17)") (class "Default")
      (node (ref "U$1") (pin "C17") (pinfunction "~{INT}_C17") (pintype "bidirectional"))
    )
    (net (code "107") (name "unconnected-(U$1-~{MREQ}-PadC14)") (class "Default")
      (node (ref "U$1") (pin "C14") (pinfunction "~{MREQ}_C14") (pintype "bidirectional"))
    )
    (net (code "108") (name "unconnected-(U$1-~{NMI}-PadC16)") (class "Default")
      (node (ref "U$1") (pin "C16") (pinfunction "~{NMI}_C16") (pintype "bidirectional"))
    )
    (net (code "109") (name "unconnected-(U$1-~{RAMCS}-PadC26)") (class "Default")
      (node (ref "U$1") (pin "C26") (pinfunction "~{RAMCS}_C26") (pintype "bidirectional"))
    )
    (net (code "110") (name "unconnected-(U$1-~{REFSH}-PadC5)") (class "Default")
      (node (ref "U$1") (pin "C5") (pinfunction "~{REFSH}_C5") (pintype "bidirectional"))
    )
    (net (code "111") (name "unconnected-(U$1-~{ROMCS}-PadA5)") (class "Default")
      (node (ref "U$1") (pin "A5") (pinfunction "~{ROMCS}_A5") (pintype "bidirectional"))
    )
    (net (code "112") (name "unconnected-(U$1-~{WAIT}-PadC9)") (class "Default")
      (node (ref "U$1") (pin "C9") (pinfunction "~{WAIT}_C9") (pintype "bidirectional"))
    )
    (net (code "113") (name "unconnected-(X1-Pad1)") (class "Default")
      (node (ref "X1") (pin "1") (pinfunction "1_1") (pintype "passive"))
    )
    (net (code "114") (name "unconnected-(X1-Pad4)") (class "Default")
      (node (ref "X1") (pin "4") (pinfunction "4_4") (pintype "passive"))
    )
    (net (code "115") (name "unconnected-(X1-Pad6)") (class "Default")
      (node (ref "X1") (pin "6") (pinfunction "6_6") (pintype "passive"))
    )
    (net (code "116") (name "unconnected-(X1-Pad9)") (class "Default")
      (node (ref "X1") (pin "9") (pinfunction "9_9") (pintype "passive"))
    )
  )
)
